# SmartMatrixSD_V2.net
KiCad netlist of a schematic drawn in EAGLE
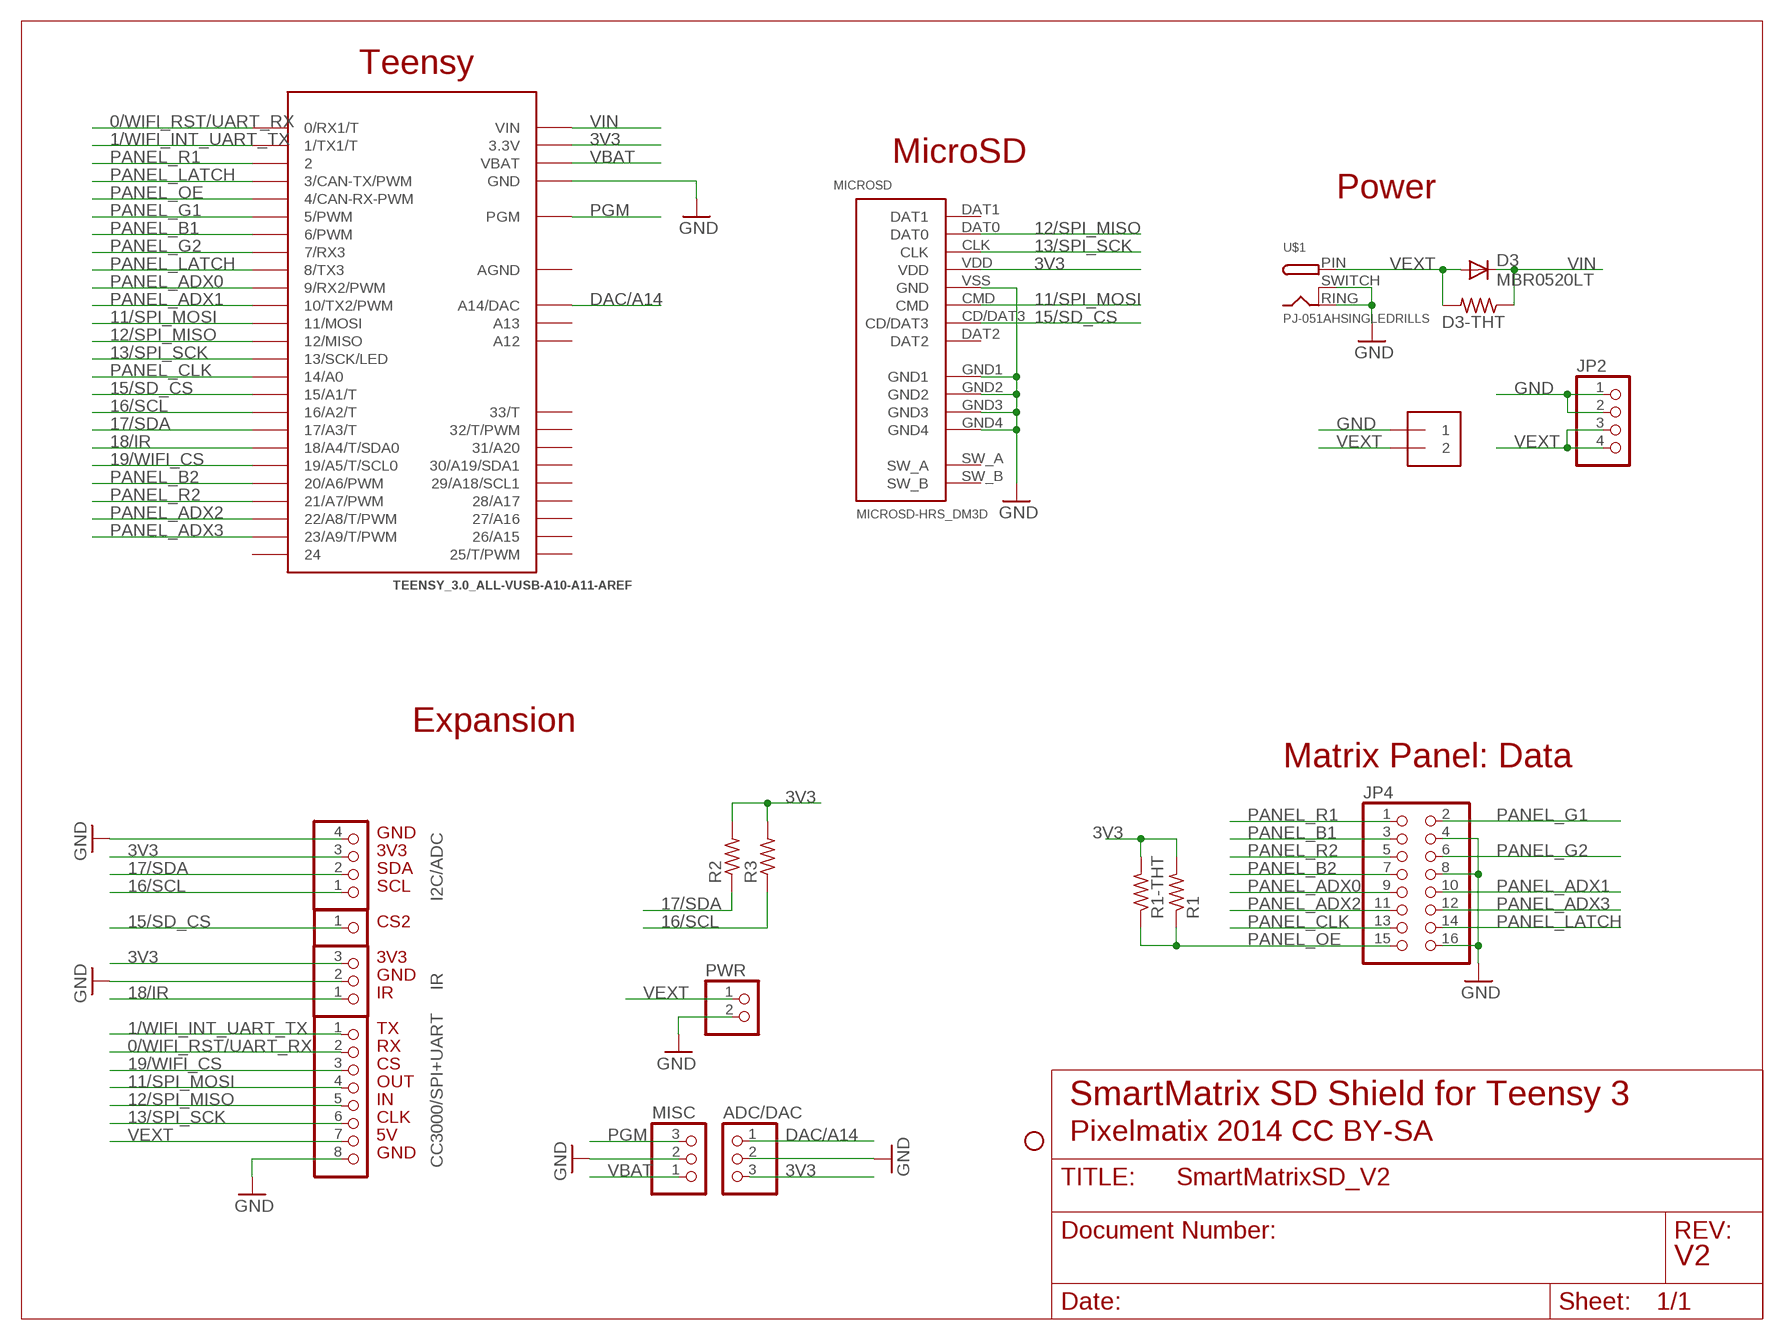
[diagram p0: schematic, sheet 1]

(export (version "E")
  (design (tool "Eeschema 10.0.6"))
  (components
    (comp (ref "ADC/DAC")
      (value "PINHD-1X03_2.54-S")
      (footprint "eagle-import:1X03-S")
      (libsource (lib "eagle-import") (part "PINHD-1X03_2.54-S"))
    )
    (comp (ref "CC3000/SPI+UART")
      (value "PINHD-1X08_2.54-S")
      (footprint "eagle-import:1X08-S")
      (libsource (lib "eagle-import") (part "PINHD-1X08_2.54-S"))
    )
    (comp (ref "CS2")
      (value "PINHD-1X01_2.54-S")
      (footprint "eagle-import:1X01-S")
      (libsource (lib "eagle-import") (part "PINHD-1X01_2.54-S"))
    )
    (comp (ref "D3")
      (value "MBR0520LT")
      (footprint "eagle-import:SOD123")
      (libsource (lib "eagle-import") (part "MBR0520LT"))
    )
    (comp (ref "D3-THT")
      (value "R-US_0207/2V")
      (footprint "eagle-import:0207_2V")
      (libsource (lib "eagle-import") (part "R-US_0207/2V"))
    )
    (comp (ref "I2C/ADC")
      (value "PINHD-1X04_2.54-S")
      (footprint "eagle-import:1X04-S")
      (libsource (lib "eagle-import") (part "pinhead-2_PINHD-1X04_2.54-S"))
    )
    (comp (ref "IR")
      (value "PINHD-1X03_2.54-S")
      (footprint "eagle-import:1X03-S")
      (libsource (lib "eagle-import") (part "PINHD-1X03_2.54-S"))
    )
    (comp (ref "J4")
      (value "1X2-5.0")
      (footprint "eagle-import:1X2-5.0MM")
      (libsource (lib "eagle-import") (part "1X2-5.0"))
    )
    (comp (ref "JP2")
      (value "PINHD-1X04_1.56")
      (footprint "eagle-import:1X04-1.56_")
      (libsource (lib "eagle-import") (part "PINHD-1X04_1.56"))
    )
    (comp (ref "JP4")
      (value "PINHD-2X08_2.54")
      (footprint "eagle-import:2X08")
      (libsource (lib "eagle-import") (part "PINHD-2X08_2.54"))
    )
    (comp (ref "JP5")
      (value "STAND-OFFSTAND-OFF-3MM")
      (footprint "eagle-import:STAND-OFF-3MM")
      (libsource (lib "eagle-import") (part "STAND-OFFSTAND-OFF-3MM"))
    )
    (comp (ref "MICROSD")
      (value "MICROSD-HRS_DM3D")
      (footprint "eagle-import:DM3D")
      (libsource (lib "eagle-import") (part "MICROSD-HRS_DM3D"))
    )
    (comp (ref "MISC")
      (value "PINHD-1X03_2.54-S")
      (footprint "eagle-import:1X03-S")
      (libsource (lib "eagle-import") (part "PINHD-1X03_2.54-S"))
    )
    (comp (ref "PWR")
      (value "PINHD-1X02_2.54-S")
      (footprint "eagle-import:1X02-S")
      (libsource (lib "eagle-import") (part "PINHD-1X02_2.54-S"))
    )
    (comp (ref "R1")
      (value "R-US_R0603")
      (footprint "eagle-import:R0603")
      (libsource (lib "eagle-import") (part "R-US_R0603"))
    )
    (comp (ref "R1-THT")
      (value "R-US_0207/2V")
      (footprint "eagle-import:0207_2V")
      (libsource (lib "eagle-import") (part "R-US_0207/2V"))
    )
    (comp (ref "R2")
      (value "R-US_0207/7")
      (footprint "eagle-import:0207_7")
      (libsource (lib "eagle-import") (part "R-US_0207/7"))
    )
    (comp (ref "R3")
      (value "R-US_0207/7")
      (footprint "eagle-import:0207_7")
      (libsource (lib "eagle-import") (part "R-US_0207/7"))
    )
    (comp (ref "TEENSY")
      (value "TEENSY_3.0_ALL-VUSB-A10-A11-AREF")
      (footprint "eagle-import:TEENSY_3.0_ALLPINS-VUSB-A11-A10-AREF")
      (libsource (lib "eagle-import") (part "TEENSY_3.0_ALL-VUSB-A10-A11-AREF"))
    )
    (comp (ref "U$1")
      (value "PJ-051AHSINGLEDRILLS")
      (footprint "eagle-import:PJ-051AH-SINGLEDRILLS")
      (libsource (lib "eagle-import") (part "PJ-051AHSINGLEDRILLS"))
    )
  )
  (nets
    (net (code "1") (name "/0{slash}WIFI_RST{slash}UART_RX") (class "Default")
      (node (ref "CC3000/SPI+UART") (pin "2") (pinfunction "2_2") (pintype "passive"))
      (node (ref "TEENSY") (pin "0") (pinfunction "0/RX1/T_0") (pintype "bidirectional"))
    )
    (net (code "2") (name "/1{slash}WIFI_INT_UART_TX") (class "Default")
      (node (ref "CC3000/SPI+UART") (pin "1") (pinfunction "1_1") (pintype "passive"))
      (node (ref "TEENSY") (pin "1") (pinfunction "1/TX1/T_1") (pintype "bidirectional"))
    )
    (net (code "3") (name "/3V3") (class "Default")
      (node (ref "ADC/DAC") (pin "3") (pinfunction "3_3") (pintype "passive"))
      (node (ref "I2C/ADC") (pin "3") (pinfunction "3_3") (pintype "passive"))
      (node (ref "IR") (pin "3") (pinfunction "3_3") (pintype "passive"))
      (node (ref "MICROSD") (pin "VDD") (pinfunction "VDD_VDD") (pintype "bidirectional"))
      (node (ref "R1") (pin "2") (pinfunction "2_2") (pintype "passive"))
      (node (ref "R1-THT") (pin "2") (pinfunction "2_2") (pintype "passive"))
      (node (ref "R2") (pin "2") (pinfunction "2_2") (pintype "passive"))
      (node (ref "R3") (pin "2") (pinfunction "2_2") (pintype "passive"))
      (node (ref "TEENSY") (pin "3.3V") (pinfunction "3.3V_3.3V") (pintype "power_in"))
      (node (ref "TEENSY") (pin "3.3V1") (pinfunction "3.3V_3.3V1") (pintype "power_in"))
      (node (ref "TEENSY") (pin "3.3V2") (pinfunction "3.3V_3.3V2") (pintype "power_in"))
    )
    (net (code "4") (name "/11{slash}SPI_MOSI") (class "Default")
      (node (ref "CC3000/SPI+UART") (pin "4") (pinfunction "4_4") (pintype "passive"))
      (node (ref "MICROSD") (pin "CMD") (pinfunction "CMD_CMD") (pintype "bidirectional"))
      (node (ref "TEENSY") (pin "11") (pinfunction "11/MOSI_11") (pintype "bidirectional"))
    )
    (net (code "5") (name "/12{slash}SPI_MISO") (class "Default")
      (node (ref "CC3000/SPI+UART") (pin "5") (pinfunction "5_5") (pintype "passive"))
      (node (ref "MICROSD") (pin "DAT0") (pinfunction "DAT0_DAT0") (pintype "bidirectional"))
      (node (ref "TEENSY") (pin "12") (pinfunction "12/MISO_12") (pintype "bidirectional"))
    )
    (net (code "6") (name "/13{slash}SPI_SCK") (class "Default")
      (node (ref "CC3000/SPI+UART") (pin "6") (pinfunction "6_6") (pintype "passive"))
      (node (ref "MICROSD") (pin "CLK") (pinfunction "CLK_CLK") (pintype "bidirectional"))
      (node (ref "TEENSY") (pin "13") (pinfunction "13/SCK/LED_13") (pintype "bidirectional"))
    )
    (net (code "7") (name "/15{slash}SD_CS") (class "Default")
      (node (ref "CS2") (pin "1") (pinfunction "1_1") (pintype "passive"))
      (node (ref "MICROSD") (pin "CD/DAT3") (pinfunction "CD/DAT3_CD/DAT3") (pintype "bidirectional"))
      (node (ref "TEENSY") (pin "15/A1") (pinfunction "15/A1/T_15/A1") (pintype "bidirectional"))
    )
    (net (code "8") (name "/16{slash}SCL") (class "Default")
      (node (ref "I2C/ADC") (pin "1") (pinfunction "1_1") (pintype "passive"))
      (node (ref "R3") (pin "1") (pinfunction "1_1") (pintype "passive"))
      (node (ref "TEENSY") (pin "16/A2") (pinfunction "16/A2/T_16/A2") (pintype "bidirectional"))
    )
    (net (code "9") (name "/17{slash}SDA") (class "Default")
      (node (ref "I2C/ADC") (pin "2") (pinfunction "2_2") (pintype "passive"))
      (node (ref "R2") (pin "1") (pinfunction "1_1") (pintype "passive"))
      (node (ref "TEENSY") (pin "17/A3") (pinfunction "17/A3/T_17/A3") (pintype "bidirectional"))
    )
    (net (code "10") (name "/18{slash}IR") (class "Default")
      (node (ref "IR") (pin "1") (pinfunction "1_1") (pintype "passive"))
      (node (ref "TEENSY") (pin "18/A4") (pinfunction "18/A4/T/SDA0_18/A4") (pintype "bidirectional"))
    )
    (net (code "11") (name "/19{slash}WIFI_CS") (class "Default")
      (node (ref "CC3000/SPI+UART") (pin "3") (pinfunction "3_3") (pintype "passive"))
      (node (ref "TEENSY") (pin "19/A5") (pinfunction "19/A5/T/SCL0_19/A5") (pintype "bidirectional"))
    )
    (net (code "12") (name "/AGND") (class "Default")
      (node (ref "TEENSY") (pin "AGND") (pinfunction "AGND_AGND") (pintype "power_in"))
    )
    (net (code "13") (name "/DAC{slash}A14") (class "Default")
      (node (ref "ADC/DAC") (pin "1") (pinfunction "1_1") (pintype "passive"))
      (node (ref "TEENSY") (pin "RESET") (pinfunction "A14/DAC_RESET") (pintype "bidirectional"))
    )
    (net (code "14") (name "/PANEL_ADX0") (class "Default")
      (node (ref "JP4") (pin "9") (pinfunction "9_9") (pintype "passive"))
      (node (ref "TEENSY") (pin "9") (pinfunction "9/RX2/PWM_9") (pintype "bidirectional"))
    )
    (net (code "15") (name "/PANEL_ADX1") (class "Default")
      (node (ref "JP4") (pin "10") (pinfunction "10_10") (pintype "passive"))
      (node (ref "TEENSY") (pin "10") (pinfunction "10/TX2/PWM_10") (pintype "bidirectional"))
    )
    (net (code "16") (name "/PANEL_ADX2") (class "Default")
      (node (ref "JP4") (pin "11") (pinfunction "11_11") (pintype "passive"))
      (node (ref "TEENSY") (pin "22/A8") (pinfunction "22/A8/T/PWM_22/A8") (pintype "bidirectional"))
    )
    (net (code "17") (name "/PANEL_ADX3") (class "Default")
      (node (ref "JP4") (pin "12") (pinfunction "12_12") (pintype "passive"))
      (node (ref "TEENSY") (pin "23/A9") (pinfunction "23/A9/T/PWM_23/A9") (pintype "bidirectional"))
    )
    (net (code "18") (name "/PANEL_B1") (class "Default")
      (node (ref "JP4") (pin "3") (pinfunction "3_3") (pintype "passive"))
      (node (ref "TEENSY") (pin "6") (pinfunction "6/PWM_6") (pintype "bidirectional"))
    )
    (net (code "19") (name "/PANEL_B2") (class "Default")
      (node (ref "JP4") (pin "7") (pinfunction "7_7") (pintype "passive"))
      (node (ref "TEENSY") (pin "20/A6") (pinfunction "20/A6/PWM_20/A6") (pintype "bidirectional"))
    )
    (net (code "20") (name "/PANEL_CLK") (class "Default")
      (node (ref "JP4") (pin "13") (pinfunction "13_13") (pintype "passive"))
      (node (ref "TEENSY") (pin "14/A0") (pinfunction "14/A0_14/A0") (pintype "bidirectional"))
    )
    (net (code "21") (name "/PANEL_G1") (class "Default")
      (node (ref "JP4") (pin "2") (pinfunction "2_2") (pintype "passive"))
      (node (ref "TEENSY") (pin "5") (pinfunction "5/PWM_5") (pintype "bidirectional"))
    )
    (net (code "22") (name "/PANEL_G2") (class "Default")
      (node (ref "JP4") (pin "6") (pinfunction "6_6") (pintype "passive"))
      (node (ref "TEENSY") (pin "7") (pinfunction "7/RX3_7") (pintype "bidirectional"))
    )
    (net (code "23") (name "/PANEL_LATCH") (class "Default")
      (node (ref "JP4") (pin "14") (pinfunction "14_14") (pintype "passive"))
      (node (ref "TEENSY") (pin "3") (pinfunction "3/CAN-TX/PWM_3") (pintype "bidirectional"))
      (node (ref "TEENSY") (pin "8") (pinfunction "8/TX3_8") (pintype "bidirectional"))
    )
    (net (code "24") (name "/PANEL_OE") (class "Default")
      (node (ref "JP4") (pin "15") (pinfunction "15_15") (pintype "passive"))
      (node (ref "R1") (pin "1") (pinfunction "1_1") (pintype "passive"))
      (node (ref "R1-THT") (pin "1") (pinfunction "1_1") (pintype "passive"))
      (node (ref "TEENSY") (pin "4") (pinfunction "4/CAN-RX-PWM_4") (pintype "bidirectional"))
    )
    (net (code "25") (name "/PANEL_R1") (class "Default")
      (node (ref "JP4") (pin "1") (pinfunction "1_1") (pintype "passive"))
      (node (ref "TEENSY") (pin "2") (pinfunction "2_2") (pintype "bidirectional"))
    )
    (net (code "26") (name "/PANEL_R2") (class "Default")
      (node (ref "JP4") (pin "5") (pinfunction "5_5") (pintype "passive"))
      (node (ref "TEENSY") (pin "21/A7") (pinfunction "21/A7/PWM_21/A7") (pintype "bidirectional"))
    )
    (net (code "27") (name "/PGM") (class "Default")
      (node (ref "MISC") (pin "3") (pinfunction "3_3") (pintype "passive"))
      (node (ref "TEENSY") (pin "PGM") (pinfunction "PGM_PGM") (pintype "bidirectional"))
    )
    (net (code "28") (name "/VBAT") (class "Default")
      (node (ref "MISC") (pin "1") (pinfunction "1_1") (pintype "passive"))
      (node (ref "TEENSY") (pin "VBAT") (pinfunction "VBAT_VBAT") (pintype "power_in"))
    )
    (net (code "29") (name "/VEXT") (class "Default")
      (node (ref "CC3000/SPI+UART") (pin "7") (pinfunction "7_7") (pintype "passive"))
      (node (ref "D3") (pin "A") (pinfunction "A_A") (pintype "passive"))
      (node (ref "D3-THT") (pin "2") (pinfunction "2_2") (pintype "passive"))
      (node (ref "J4") (pin "2") (pinfunction "2_2") (pintype "passive"))
      (node (ref "JP2") (pin "3") (pinfunction "3_3") (pintype "passive"))
      (node (ref "JP2") (pin "4") (pinfunction "4_4") (pintype "passive"))
      (node (ref "PWR") (pin "1") (pinfunction "1_1") (pintype "passive"))
      (node (ref "U$1") (pin "PIN") (pinfunction "PWR_PIN") (pintype "power_in"))
    )
    (net (code "30") (name "/VIN") (class "Default")
      (node (ref "D3") (pin "C") (pinfunction "C_C") (pintype "passive"))
      (node (ref "D3-THT") (pin "1") (pinfunction "1_1") (pintype "passive"))
      (node (ref "TEENSY") (pin "VIN") (pinfunction "VIN_VIN") (pintype "power_in"))
    )
    (net (code "31") (name "GND") (class "Default")
      (node (ref "ADC/DAC") (pin "2") (pinfunction "2_2") (pintype "passive"))
      (node (ref "CC3000/SPI+UART") (pin "8") (pinfunction "8_8") (pintype "passive"))
      (node (ref "I2C/ADC") (pin "4") (pinfunction "4_4") (pintype "passive"))
      (node (ref "IR") (pin "2") (pinfunction "2_2") (pintype "passive"))
      (node (ref "J4") (pin "1") (pinfunction "1_1") (pintype "passive"))
      (node (ref "JP2") (pin "1") (pinfunction "1_1") (pintype "passive"))
      (node (ref "JP2") (pin "2") (pinfunction "2_2") (pintype "passive"))
      (node (ref "JP4") (pin "16") (pinfunction "16_16") (pintype "passive"))
      (node (ref "JP4") (pin "4") (pinfunction "4_4") (pintype "passive"))
      (node (ref "JP4") (pin "8") (pinfunction "8_8") (pintype "passive"))
      (node (ref "MICROSD") (pin "GND1") (pinfunction "GND1_GND1") (pintype "bidirectional"))
      (node (ref "MICROSD") (pin "GND2") (pinfunction "GND2_GND2") (pintype "bidirectional"))
      (node (ref "MICROSD") (pin "GND3") (pinfunction "GND3_GND3") (pintype "bidirectional"))
      (node (ref "MICROSD") (pin "GND4") (pinfunction "GND4_GND4") (pintype "bidirectional"))
      (node (ref "MICROSD") (pin "VSS") (pinfunction "GND_VSS") (pintype "bidirectional"))
      (node (ref "MISC") (pin "2") (pinfunction "2_2") (pintype "passive"))
      (node (ref "PWR") (pin "2") (pinfunction "2_2") (pintype "passive"))
      (node (ref "TEENSY") (pin "GND") (pinfunction "GND_GND") (pintype "power_in"))
      (node (ref "TEENSY") (pin "GND1") (pinfunction "GND_GND1") (pintype "power_in"))
      (node (ref "TEENSY") (pin "GND2") (pinfunction "GND_GND2") (pintype "power_in"))
      (node (ref "U$1") (pin "RING") (pinfunction "GND_RING") (pintype "power_in"))
      (node (ref "U$1") (pin "SWITCH") (pinfunction "GNDBREAK_SWITCH") (pintype "power_in"))
    )
    (net (code "32") (name "unconnected-(MICROSD-PadDAT1)") (class "Default")
      (node (ref "MICROSD") (pin "DAT1") (pinfunction "DAT1_DAT1") (pintype "bidirectional"))
    )
    (net (code "33") (name "unconnected-(MICROSD-PadDAT2)") (class "Default")
      (node (ref "MICROSD") (pin "DAT2") (pinfunction "DAT2_DAT2") (pintype "bidirectional"))
    )
    (net (code "34") (name "unconnected-(MICROSD-PadSW_A)") (class "Default")
      (node (ref "MICROSD") (pin "SW_A") (pinfunction "SW_A_SW_A") (pintype "bidirectional"))
    )
    (net (code "35") (name "unconnected-(MICROSD-PadSW_B)") (class "Default")
      (node (ref "MICROSD") (pin "SW_B") (pinfunction "SW_B_SW_B") (pintype "bidirectional"))
    )
    (net (code "36") (name "unconnected-(TEENSY-25{slash}T{slash}PWM-Pad25)") (class "Default")
      (node (ref "TEENSY") (pin "25") (pinfunction "25/T/PWM_25") (pintype "bidirectional"))
    )
    (net (code "37") (name "unconnected-(TEENSY-26{slash}A15-Pad26)") (class "Default")
      (node (ref "TEENSY") (pin "26") (pinfunction "26/A15_26") (pintype "bidirectional"))
    )
    (net (code "38") (name "unconnected-(TEENSY-27{slash}A16-Pad27)") (class "Default")
      (node (ref "TEENSY") (pin "27") (pinfunction "27/A16_27") (pintype "bidirectional"))
    )
    (net (code "39") (name "unconnected-(TEENSY-28{slash}A17-Pad28)") (class "Default")
      (node (ref "TEENSY") (pin "28") (pinfunction "28/A17_28") (pintype "bidirectional"))
    )
    (net (code "40") (name "unconnected-(TEENSY-29{slash}A18{slash}SCL1-Pad29)") (class "Default")
      (node (ref "TEENSY") (pin "29") (pinfunction "29/A18/SCL1_29") (pintype "bidirectional"))
    )
    (net (code "41") (name "unconnected-(TEENSY-30{slash}A19{slash}SDA1-Pad30)") (class "Default")
      (node (ref "TEENSY") (pin "30") (pinfunction "30/A19/SDA1_30") (pintype "bidirectional"))
    )
    (net (code "42") (name "unconnected-(TEENSY-31{slash}A20-Pad31)") (class "Default")
      (node (ref "TEENSY") (pin "31") (pinfunction "31/A20_31") (pintype "bidirectional"))
    )
    (net (code "43") (name "unconnected-(TEENSY-32{slash}T{slash}PWM-Pad32)") (class "Default")
      (node (ref "TEENSY") (pin "32") (pinfunction "32/T/PWM_32") (pintype "bidirectional"))
    )
    (net (code "44") (name "unconnected-(TEENSY-33{slash}T-Pad33)") (class "Default")
      (node (ref "TEENSY") (pin "33") (pinfunction "33/T_33") (pintype "bidirectional"))
    )
    (net (code "45") (name "unconnected-(TEENSY-Pad24)") (class "Default")
      (node (ref "TEENSY") (pin "24") (pinfunction "24_24") (pintype "bidirectional"))
    )
    (net (code "46") (name "unconnected-(TEENSY-PadA12)") (class "Default")
      (node (ref "TEENSY") (pin "A12") (pinfunction "A12_A12") (pintype "bidirectional"))
    )
    (net (code "47") (name "unconnected-(TEENSY-PadA13)") (class "Default")
      (node (ref "TEENSY") (pin "A13") (pinfunction "A13_A13") (pintype "bidirectional"))
    )
  )
)
